# senzory.net
KiCad netlist of a schematic drawn in EAGLE
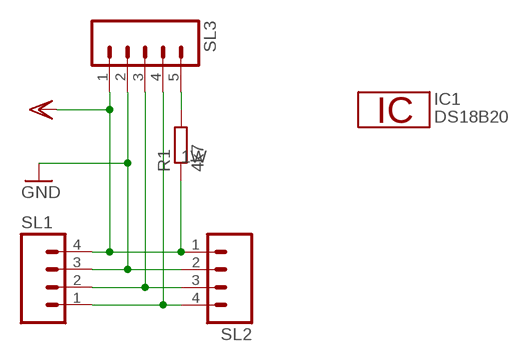
[diagram p0: schematic, sheet 1]

(export (version "E")
  (design (tool "Eeschema 10.0.6"))
  (components
    (comp (ref "IC1")
      (value "DS18B20")
      (footprint "eagle-import:TO92-")
      (libsource (lib "eagle-import") (part "DS18B20"))
    )
    (comp (ref "R1")
      (value "4k7")
      (footprint "eagle-import:0204_7")
      (libsource (lib "eagle-import") (part "R-EU_0204/7"))
    )
    (comp (ref "SL1")
      (value "M04")
      (footprint "eagle-import:04P")
      (libsource (lib "eagle-import") (part "M04"))
    )
    (comp (ref "SL2")
      (value "M04")
      (footprint "eagle-import:04P")
      (libsource (lib "eagle-import") (part "M04"))
    )
    (comp (ref "SL3")
      (value "M05")
      (footprint "eagle-import:05P")
      (libsource (lib "eagle-import") (part "M05"))
    )
  )
  (nets
    (net (code "1") (name "/1W") (class "Default")
      (node (ref "R1") (pin "2") (pinfunction "2_2") (pintype "passive"))
      (node (ref "SL3") (pin "5") (pinfunction "5_5") (pintype "passive"))
    )
    (net (code "2") (name "GND") (class "Default")
      (node (ref "SL1") (pin "3") (pinfunction "3_3") (pintype "passive"))
      (node (ref "SL2") (pin "2") (pinfunction "2_2") (pintype "passive"))
      (node (ref "SL3") (pin "2") (pinfunction "2_2") (pintype "passive"))
    )
    (net (code "3") (name "Net-(SL1-Pad1)") (class "Default")
      (node (ref "SL1") (pin "1") (pinfunction "1_1") (pintype "passive"))
      (node (ref "SL2") (pin "4") (pinfunction "4_4") (pintype "passive"))
      (node (ref "SL3") (pin "4") (pinfunction "4_4") (pintype "passive"))
    )
    (net (code "4") (name "Net-(SL1-Pad2)") (class "Default")
      (node (ref "SL1") (pin "2") (pinfunction "2_2") (pintype "passive"))
      (node (ref "SL2") (pin "3") (pinfunction "3_3") (pintype "passive"))
      (node (ref "SL3") (pin "3") (pinfunction "3_3") (pintype "passive"))
    )
    (net (code "5") (name "VDD") (class "Default")
      (node (ref "R1") (pin "1") (pinfunction "1_1") (pintype "passive"))
      (node (ref "SL1") (pin "4") (pinfunction "4_4") (pintype "passive"))
      (node (ref "SL2") (pin "1") (pinfunction "1_1") (pintype "passive"))
      (node (ref "SL3") (pin "1") (pinfunction "1_1") (pintype "passive"))
    )
  )
)
